# Binary_Sequencer_board1_Arduino.net
KiCad netlist of a schematic drawn in EAGLE
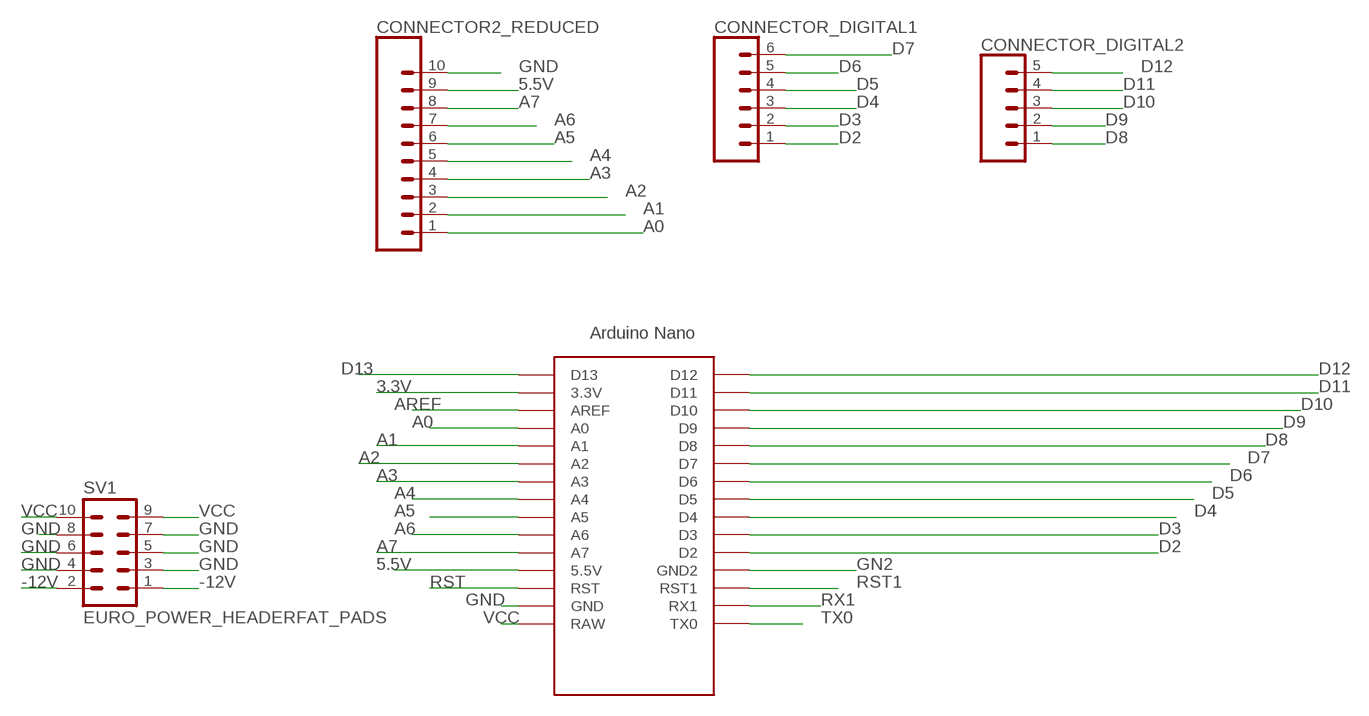
[diagram p0: schematic, sheet 1]

(export (version "E")
  (design (tool "Eeschema 10.0.6"))
  (components
    (comp (ref "CONNECTOR2_REDUCED")
      (value "CONN_10_LONGPADS10_LONGPADS")
      (footprint "eagle-import:1X10_LONGPADS")
      (libsource (lib "eagle-import") (part "CONN_10_LONGPADS10_LONGPADS"))
    )
    (comp (ref "CONNECTOR_DIGITAL1")
      (value "CONN_06LONGPADS")
      (footprint "eagle-import:1X06_LONGPADS")
      (libsource (lib "eagle-import") (part "CONN_06LONGPADS"))
    )
    (comp (ref "CONNECTOR_DIGITAL2")
      (value "CONN_05PTH_LONGPADS")
      (footprint "eagle-import:1X05_LONGPADS")
      (libsource (lib "eagle-import") (part "CONN_05PTH_LONGPADS"))
    )
    (comp (ref "SV1")
      (value "EURO_POWER_HEADERFAT_PADS")
      (footprint "eagle-import:EURO_PWR_HEADER_FAT")
      (libsource (lib "eagle-import") (part "EURO_POWER_HEADERFAT_PADS"))
    )
    (comp (ref "U$1")
      (value "NANO")
      (footprint "eagle-import:NANO")
      (libsource (lib "eagle-import") (part "NANO"))
    )
  )
  (nets
    (net (code "1") (name "/-12V") (class "Default")
      (node (ref "SV1") (pin "1") (pinfunction "1_1") (pintype "passive"))
      (node (ref "SV1") (pin "2") (pinfunction "2_2") (pintype "passive"))
    )
    (net (code "2") (name "/3.3V") (class "Default")
      (node (ref "U$1") (pin "3.3V") (pinfunction "3.3V_3.3V") (pintype "bidirectional"))
    )
    (net (code "3") (name "/5.5V") (class "Default")
      (node (ref "CONNECTOR2_REDUCED") (pin "9") (pinfunction "9_9") (pintype "passive"))
      (node (ref "U$1") (pin "5V") (pinfunction "5.5V_5V") (pintype "bidirectional"))
    )
    (net (code "4") (name "/A0") (class "Default")
      (node (ref "CONNECTOR2_REDUCED") (pin "1") (pinfunction "1_1") (pintype "passive"))
      (node (ref "U$1") (pin "A0") (pinfunction "A0_A0") (pintype "bidirectional"))
    )
    (net (code "5") (name "/A1") (class "Default")
      (node (ref "CONNECTOR2_REDUCED") (pin "2") (pinfunction "2_2") (pintype "passive"))
      (node (ref "U$1") (pin "A1") (pinfunction "A1_A1") (pintype "bidirectional"))
    )
    (net (code "6") (name "/A2") (class "Default")
      (node (ref "CONNECTOR2_REDUCED") (pin "3") (pinfunction "3_3") (pintype "passive"))
      (node (ref "U$1") (pin "A2") (pinfunction "A2_A2") (pintype "bidirectional"))
    )
    (net (code "7") (name "/A3") (class "Default")
      (node (ref "CONNECTOR2_REDUCED") (pin "4") (pinfunction "4_4") (pintype "passive"))
      (node (ref "U$1") (pin "A3") (pinfunction "A3_A3") (pintype "bidirectional"))
    )
    (net (code "8") (name "/A4") (class "Default")
      (node (ref "CONNECTOR2_REDUCED") (pin "5") (pinfunction "5_5") (pintype "passive"))
      (node (ref "U$1") (pin "A4") (pinfunction "A4_A4") (pintype "bidirectional"))
    )
    (net (code "9") (name "/A5") (class "Default")
      (node (ref "CONNECTOR2_REDUCED") (pin "6") (pinfunction "6_6") (pintype "passive"))
      (node (ref "U$1") (pin "A5") (pinfunction "A5_A5") (pintype "bidirectional"))
    )
    (net (code "10") (name "/A6") (class "Default")
      (node (ref "CONNECTOR2_REDUCED") (pin "7") (pinfunction "7_7") (pintype "passive"))
      (node (ref "U$1") (pin "A6") (pinfunction "A6_A6") (pintype "bidirectional"))
    )
    (net (code "11") (name "/A7") (class "Default")
      (node (ref "CONNECTOR2_REDUCED") (pin "8") (pinfunction "8_8") (pintype "passive"))
      (node (ref "U$1") (pin "A7") (pinfunction "A7_A7") (pintype "bidirectional"))
    )
    (net (code "12") (name "/AREF") (class "Default")
      (node (ref "U$1") (pin "AREF") (pinfunction "AREF_AREF") (pintype "bidirectional"))
    )
    (net (code "13") (name "/D2") (class "Default")
      (node (ref "CONNECTOR_DIGITAL1") (pin "1") (pinfunction "1_1") (pintype "passive"))
      (node (ref "U$1") (pin "D2") (pinfunction "D2_D2") (pintype "bidirectional"))
    )
    (net (code "14") (name "/D3") (class "Default")
      (node (ref "CONNECTOR_DIGITAL1") (pin "2") (pinfunction "2_2") (pintype "passive"))
      (node (ref "U$1") (pin "D3") (pinfunction "D3_D3") (pintype "bidirectional"))
    )
    (net (code "15") (name "/D4") (class "Default")
      (node (ref "CONNECTOR_DIGITAL1") (pin "3") (pinfunction "3_3") (pintype "passive"))
      (node (ref "U$1") (pin "D4") (pinfunction "D4_D4") (pintype "bidirectional"))
    )
    (net (code "16") (name "/D5") (class "Default")
      (node (ref "CONNECTOR_DIGITAL1") (pin "4") (pinfunction "4_4") (pintype "passive"))
      (node (ref "U$1") (pin "D5") (pinfunction "D5_D5") (pintype "bidirectional"))
    )
    (net (code "17") (name "/D6") (class "Default")
      (node (ref "CONNECTOR_DIGITAL1") (pin "5") (pinfunction "5_5") (pintype "passive"))
      (node (ref "U$1") (pin "D6") (pinfunction "D6_D6") (pintype "bidirectional"))
    )
    (net (code "18") (name "/D7") (class "Default")
      (node (ref "CONNECTOR_DIGITAL1") (pin "6") (pinfunction "6_6") (pintype "passive"))
      (node (ref "U$1") (pin "D7") (pinfunction "D7_D7") (pintype "bidirectional"))
    )
    (net (code "19") (name "/D8") (class "Default")
      (node (ref "CONNECTOR_DIGITAL2") (pin "1") (pinfunction "1_1") (pintype "passive"))
      (node (ref "U$1") (pin "D8") (pinfunction "D8_D8") (pintype "bidirectional"))
    )
    (net (code "20") (name "/D9") (class "Default")
      (node (ref "CONNECTOR_DIGITAL2") (pin "2") (pinfunction "2_2") (pintype "passive"))
      (node (ref "U$1") (pin "D9") (pinfunction "D9_D9") (pintype "bidirectional"))
    )
    (net (code "21") (name "/D10") (class "Default")
      (node (ref "CONNECTOR_DIGITAL2") (pin "3") (pinfunction "3_3") (pintype "passive"))
      (node (ref "U$1") (pin "D10") (pinfunction "D10_D10") (pintype "bidirectional"))
    )
    (net (code "22") (name "/D11") (class "Default")
      (node (ref "CONNECTOR_DIGITAL2") (pin "4") (pinfunction "4_4") (pintype "passive"))
      (node (ref "U$1") (pin "D11") (pinfunction "D11_D11") (pintype "bidirectional"))
    )
    (net (code "23") (name "/D12") (class "Default")
      (node (ref "CONNECTOR_DIGITAL2") (pin "5") (pinfunction "5_5") (pintype "passive"))
      (node (ref "U$1") (pin "D12") (pinfunction "D12_D12") (pintype "bidirectional"))
    )
    (net (code "24") (name "/D13") (class "Default")
      (node (ref "U$1") (pin "D13") (pinfunction "D13_D13") (pintype "bidirectional"))
    )
    (net (code "25") (name "/GN2") (class "Default")
      (node (ref "U$1") (pin "GND1") (pinfunction "GND2_GND1") (pintype "bidirectional"))
    )
    (net (code "26") (name "/GND") (class "Default")
      (node (ref "CONNECTOR2_REDUCED") (pin "10") (pinfunction "10_10") (pintype "passive"))
      (node (ref "SV1") (pin "3") (pinfunction "3_3") (pintype "passive"))
      (node (ref "SV1") (pin "4") (pinfunction "4_4") (pintype "passive"))
      (node (ref "SV1") (pin "5") (pinfunction "5_5") (pintype "passive"))
      (node (ref "SV1") (pin "6") (pinfunction "6_6") (pintype "passive"))
      (node (ref "SV1") (pin "7") (pinfunction "7_7") (pintype "passive"))
      (node (ref "SV1") (pin "8") (pinfunction "8_8") (pintype "passive"))
      (node (ref "U$1") (pin "GND") (pinfunction "GND_GND") (pintype "bidirectional"))
    )
    (net (code "27") (name "/RST") (class "Default")
      (node (ref "U$1") (pin "RST") (pinfunction "RST_RST") (pintype "bidirectional"))
    )
    (net (code "28") (name "/RST1") (class "Default")
      (node (ref "U$1") (pin "RST1") (pinfunction "RST1_RST1") (pintype "bidirectional"))
    )
    (net (code "29") (name "/RX1") (class "Default")
      (node (ref "U$1") (pin "RX1") (pinfunction "RX1_RX1") (pintype "bidirectional"))
    )
    (net (code "30") (name "/TX0") (class "Default")
      (node (ref "U$1") (pin "TX0") (pinfunction "TX0_TX0") (pintype "bidirectional"))
    )
    (net (code "31") (name "/VCC") (class "Default")
      (node (ref "SV1") (pin "10") (pinfunction "10_10") (pintype "passive"))
      (node (ref "SV1") (pin "9") (pinfunction "9_9") (pintype "passive"))
      (node (ref "U$1") (pin "RAW") (pinfunction "RAW_RAW") (pintype "bidirectional"))
    )
  )
)
